# ADS1232_interface.net
KiCad netlist of a schematic drawn in EAGLE
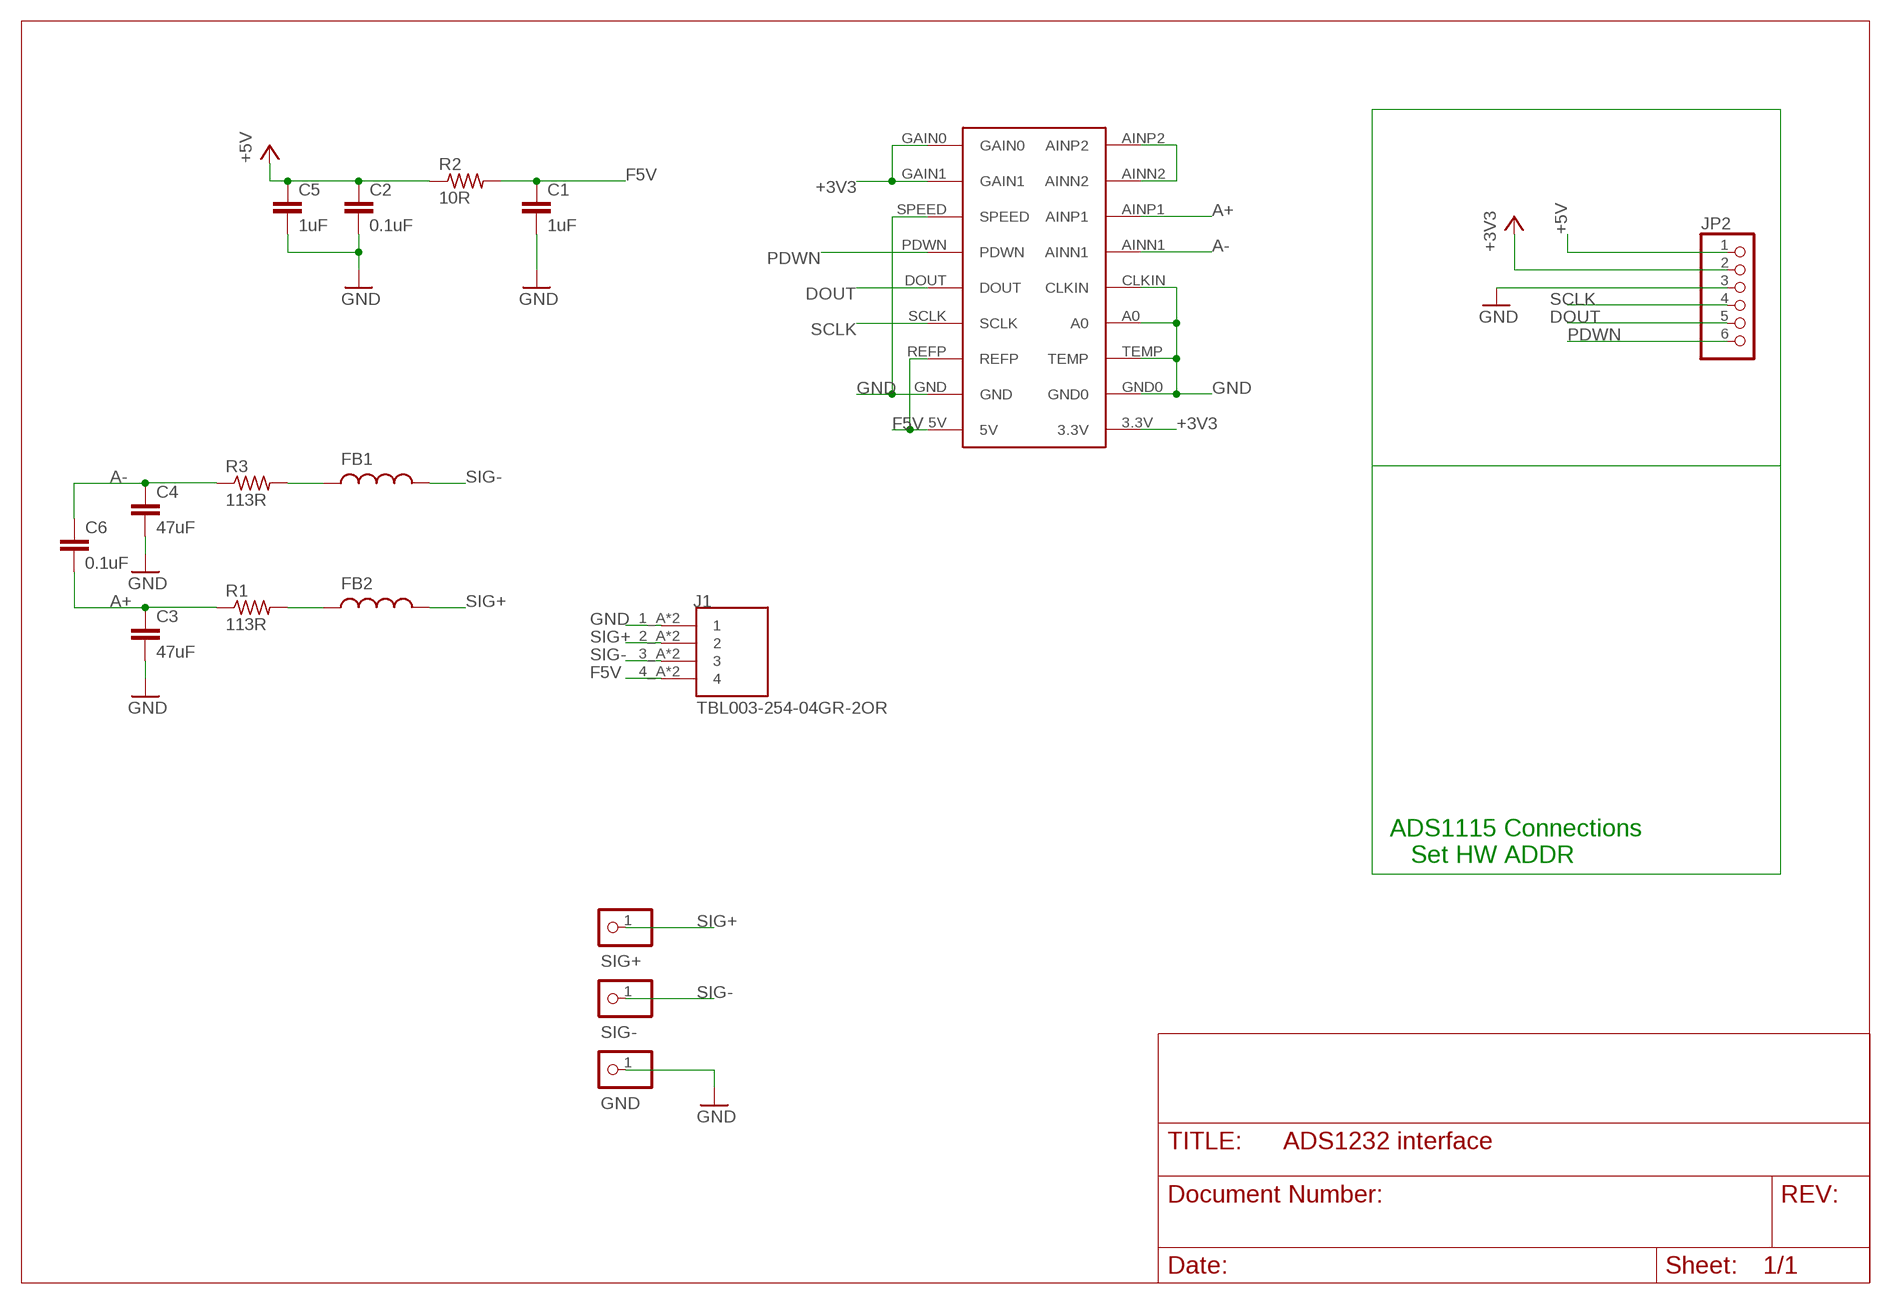
[diagram p0: schematic, sheet 1]

(export (version "E")
  (design (tool "Eeschema 10.0.6"))
  (components
    (comp (ref "ADS1232")
      (value "ADS1232")
      (footprint "eagle-import:ADS1232")
      (libsource (lib "eagle-import") (part "ADS1232"))
    )
    (comp (ref "C1")
      (value "1uF")
      (footprint "eagle-import:C0805")
      (libsource (lib "eagle-import") (part "C-EUC0805"))
    )
    (comp (ref "C2")
      (value "0.1uF")
      (footprint "eagle-import:C0805")
      (libsource (lib "eagle-import") (part "C-EUC0805"))
    )
    (comp (ref "C3")
      (value "47uF")
      (footprint "eagle-import:C0805")
      (libsource (lib "eagle-import") (part "C-EUC0805"))
    )
    (comp (ref "C4")
      (value "47uF")
      (footprint "eagle-import:C0805")
      (libsource (lib "eagle-import") (part "C-EUC0805"))
    )
    (comp (ref "C5")
      (value "1uF")
      (footprint "eagle-import:C0805")
      (libsource (lib "eagle-import") (part "C-EUC0805"))
    )
    (comp (ref "C6")
      (value "0.1uF")
      (footprint "eagle-import:C0805")
      (libsource (lib "eagle-import") (part "C-EUC0805"))
    )
    (comp (ref "FB1")
      (value "WE-RFI_0805A_744760282A")
      (footprint "eagle-import:WE-RFI_0805A")
      (libsource (lib "eagle-import") (part "WE-RFI_0805A_744760282A"))
    )
    (comp (ref "FB2")
      (value "WE-RFI_0805A_744760282A")
      (footprint "eagle-import:WE-RFI_0805A")
      (libsource (lib "eagle-import") (part "WE-RFI_0805A_744760282A"))
    )
    (comp (ref "GND")
      (value "PINHD-1X1")
      (footprint "eagle-import:1X01")
      (libsource (lib "eagle-import") (part "PINHD-1X1"))
    )
    (comp (ref "J1")
      (value "TBL003-254-04GR-2OR")
      (footprint "eagle-import:CUI_TBL003-254-04GR-2OR")
      (fields (field (name "MF") "CUI Devices"))
      (libsource (lib "eagle-import") (part "TBL003-254-04GR-2OR"))
    )
    (comp (ref "JP2")
      (value "PINHD-1X6")
      (footprint "eagle-import:1X06")
      (libsource (lib "eagle-import") (part "PINHD-1X6"))
    )
    (comp (ref "R1")
      (value "113R")
      (footprint "eagle-import:R0805")
      (libsource (lib "eagle-import") (part "R-US_R0805"))
    )
    (comp (ref "R2")
      (value "10R")
      (footprint "eagle-import:R0805")
      (libsource (lib "eagle-import") (part "R-US_R0805"))
    )
    (comp (ref "R3")
      (value "113R")
      (footprint "eagle-import:R0805")
      (libsource (lib "eagle-import") (part "R-US_R0805"))
    )
    (comp (ref "SIG+")
      (value "PINHD-1X1")
      (footprint "eagle-import:1X01")
      (libsource (lib "eagle-import") (part "PINHD-1X1"))
    )
    (comp (ref "SIG-")
      (value "PINHD-1X1")
      (footprint "eagle-import:1X01")
      (libsource (lib "eagle-import") (part "PINHD-1X1"))
    )
  )
  (nets
    (net (code "1") (name "+3V3") (class "Default")
      (node (ref "ADS1232") (pin "3.3V") (pinfunction "3.3V_3.3V") (pintype "bidirectional"))
      (node (ref "ADS1232") (pin "GAIN0") (pinfunction "GAIN0_GAIN0") (pintype "bidirectional"))
      (node (ref "ADS1232") (pin "GAIN1") (pinfunction "GAIN1_GAIN1") (pintype "bidirectional"))
      (node (ref "JP2") (pin "2") (pinfunction "2_2") (pintype "passive"))
    )
    (net (code "2") (name "+5V") (class "Default")
      (node (ref "C2") (pin "1") (pinfunction "1_1") (pintype "passive"))
      (node (ref "C5") (pin "1") (pinfunction "1_1") (pintype "passive"))
      (node (ref "JP2") (pin "1") (pinfunction "1_1") (pintype "passive"))
      (node (ref "R2") (pin "1") (pinfunction "1_1") (pintype "passive"))
    )
    (net (code "3") (name "/A+") (class "Default")
      (node (ref "ADS1232") (pin "AINP1") (pinfunction "AINP1_AINP1") (pintype "bidirectional"))
      (node (ref "C3") (pin "1") (pinfunction "1_1") (pintype "passive"))
      (node (ref "C6") (pin "2") (pinfunction "2_2") (pintype "passive"))
      (node (ref "R1") (pin "1") (pinfunction "1_1") (pintype "passive"))
    )
    (net (code "4") (name "/A-") (class "Default")
      (node (ref "ADS1232") (pin "AINN1") (pinfunction "AINN1_AINN1") (pintype "bidirectional"))
      (node (ref "C4") (pin "1") (pinfunction "1_1") (pintype "passive"))
      (node (ref "C6") (pin "1") (pinfunction "1_1") (pintype "passive"))
      (node (ref "R3") (pin "1") (pinfunction "1_1") (pintype "passive"))
    )
    (net (code "5") (name "/DOUT") (class "Default")
      (node (ref "ADS1232") (pin "DOUT") (pinfunction "DOUT_DOUT") (pintype "bidirectional"))
      (node (ref "JP2") (pin "5") (pinfunction "5_5") (pintype "passive"))
    )
    (net (code "6") (name "/F5V") (class "Default")
      (node (ref "ADS1232") (pin "5V") (pinfunction "5V_5V") (pintype "bidirectional"))
      (node (ref "ADS1232") (pin "REFP") (pinfunction "REFP_REFP") (pintype "bidirectional"))
      (node (ref "C1") (pin "1") (pinfunction "1_1") (pintype "passive"))
      (node (ref "J1") (pin "4_A") (pinfunction "4_4_A") (pintype "passive"))
      (node (ref "J1") (pin "4_B") (pinfunction "4_4_B") (pintype "passive"))
      (node (ref "R2") (pin "2") (pinfunction "2_2") (pintype "passive"))
    )
    (net (code "7") (name "/PDWN") (class "Default")
      (node (ref "ADS1232") (pin "PDWN") (pinfunction "PDWN_PDWN") (pintype "bidirectional"))
      (node (ref "JP2") (pin "6") (pinfunction "6_6") (pintype "passive"))
    )
    (net (code "8") (name "/SCLK") (class "Default")
      (node (ref "ADS1232") (pin "SCLK") (pinfunction "SCLK_SCLK") (pintype "bidirectional"))
      (node (ref "JP2") (pin "4") (pinfunction "4_4") (pintype "passive"))
    )
    (net (code "9") (name "/SIG+") (class "Default")
      (node (ref "FB2") (pin "2") (pinfunction "2_2") (pintype "passive"))
      (node (ref "J1") (pin "2_A") (pinfunction "2_2_A") (pintype "passive"))
      (node (ref "J1") (pin "2_B") (pinfunction "2_2_B") (pintype "passive"))
      (node (ref "SIG+") (pin "1") (pinfunction "1_1") (pintype "passive"))
    )
    (net (code "10") (name "/SIG-") (class "Default")
      (node (ref "FB1") (pin "2") (pinfunction "2_2") (pintype "passive"))
      (node (ref "J1") (pin "3_A") (pinfunction "3_3_A") (pintype "passive"))
      (node (ref "J1") (pin "3_B") (pinfunction "3_3_B") (pintype "passive"))
      (node (ref "SIG-") (pin "1") (pinfunction "1_1") (pintype "passive"))
    )
    (net (code "11") (name "GND") (class "Default")
      (node (ref "ADS1232") (pin "A0") (pinfunction "A0_A0") (pintype "bidirectional"))
      (node (ref "ADS1232") (pin "AINN2") (pinfunction "AINN2_AINN2") (pintype "bidirectional"))
      (node (ref "ADS1232") (pin "AINP2") (pinfunction "AINP2_AINP2") (pintype "bidirectional"))
      (node (ref "ADS1232") (pin "CLKIN") (pinfunction "CLKIN_CLKIN") (pintype "bidirectional"))
      (node (ref "ADS1232") (pin "GND") (pinfunction "GND_GND") (pintype "bidirectional"))
      (node (ref "ADS1232") (pin "GND0") (pinfunction "GND0_GND0") (pintype "bidirectional"))
      (node (ref "ADS1232") (pin "SPEED") (pinfunction "SPEED_SPEED") (pintype "bidirectional"))
      (node (ref "ADS1232") (pin "TEMP") (pinfunction "TEMP_TEMP") (pintype "bidirectional"))
      (node (ref "C1") (pin "2") (pinfunction "2_2") (pintype "passive"))
      (node (ref "C2") (pin "2") (pinfunction "2_2") (pintype "passive"))
      (node (ref "C3") (pin "2") (pinfunction "2_2") (pintype "passive"))
      (node (ref "C4") (pin "2") (pinfunction "2_2") (pintype "passive"))
      (node (ref "C5") (pin "2") (pinfunction "2_2") (pintype "passive"))
      (node (ref "GND") (pin "1") (pinfunction "1_1") (pintype "passive"))
      (node (ref "J1") (pin "1_A") (pinfunction "1_1_A") (pintype "passive"))
      (node (ref "J1") (pin "1_B") (pinfunction "1_1_B") (pintype "passive"))
      (node (ref "JP2") (pin "3") (pinfunction "3_3") (pintype "passive"))
    )
    (net (code "12") (name "Net-(FB1-Pad1)") (class "Default")
      (node (ref "FB1") (pin "1") (pinfunction "1_1") (pintype "passive"))
      (node (ref "R3") (pin "2") (pinfunction "2_2") (pintype "passive"))
    )
    (net (code "13") (name "Net-(FB2-Pad1)") (class "Default")
      (node (ref "FB2") (pin "1") (pinfunction "1_1") (pintype "passive"))
      (node (ref "R1") (pin "2") (pinfunction "2_2") (pintype "passive"))
    )
  )
)
